# 20V-3V3-Divider.net
KiCad netlist of a schematic drawn in EAGLE
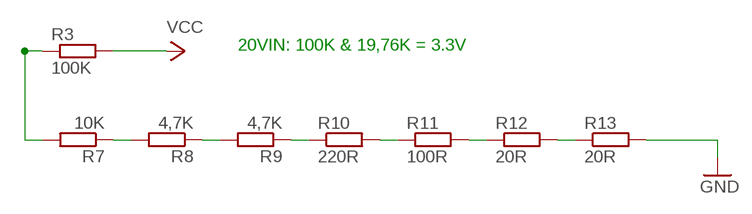
[diagram p0: schematic, sheet 1]

(export (version "E")
  (design (tool "Eeschema 10.0.6"))
  (components
    (comp (ref "R3")
      (value "100K")
      (footprint "eagle-import:0204_7")
      (libsource (lib "eagle-import") (part "R-EU_0204/7"))
    )
    (comp (ref "R7")
      (value "10K")
      (footprint "eagle-import:0204_7")
      (libsource (lib "eagle-import") (part "R-EU_0204/7"))
    )
    (comp (ref "R8")
      (value "4,7K")
      (footprint "eagle-import:0204_7")
      (libsource (lib "eagle-import") (part "R-EU_0204/7"))
    )
    (comp (ref "R9")
      (value "4,7K")
      (footprint "eagle-import:0204_7")
      (libsource (lib "eagle-import") (part "R-EU_0204/7"))
    )
    (comp (ref "R10")
      (value "220R")
      (footprint "eagle-import:0204_7")
      (libsource (lib "eagle-import") (part "R-EU_0204/7"))
    )
    (comp (ref "R11")
      (value "100R")
      (footprint "eagle-import:0204_7")
      (libsource (lib "eagle-import") (part "R-EU_0204/7"))
    )
    (comp (ref "R12")
      (value "20R")
      (footprint "eagle-import:0204_7")
      (libsource (lib "eagle-import") (part "R-EU_0204/7"))
    )
    (comp (ref "R13")
      (value "20R")
      (footprint "eagle-import:0204_7")
      (libsource (lib "eagle-import") (part "R-EU_0204/7"))
    )
  )
  (nets
    (net (code "1") (name "GND") (class "Default")
      (node (ref "R13") (pin "2") (pinfunction "2_2") (pintype "passive"))
    )
    (net (code "2") (name "Net-(R3-Pad1)") (class "Default")
      (node (ref "R3") (pin "1") (pinfunction "1_1") (pintype "passive"))
      (node (ref "R7") (pin "2") (pinfunction "2_2") (pintype "passive"))
    )
    (net (code "3") (name "Net-(R7-Pad1)") (class "Default")
      (node (ref "R7") (pin "1") (pinfunction "1_1") (pintype "passive"))
      (node (ref "R8") (pin "2") (pinfunction "2_2") (pintype "passive"))
    )
    (net (code "4") (name "Net-(R8-Pad1)") (class "Default")
      (node (ref "R8") (pin "1") (pinfunction "1_1") (pintype "passive"))
      (node (ref "R9") (pin "2") (pinfunction "2_2") (pintype "passive"))
    )
    (net (code "5") (name "Net-(R10-Pad1)") (class "Default")
      (node (ref "R10") (pin "1") (pinfunction "1_1") (pintype "passive"))
      (node (ref "R9") (pin "1") (pinfunction "1_1") (pintype "passive"))
    )
    (net (code "6") (name "Net-(R10-Pad2)") (class "Default")
      (node (ref "R10") (pin "2") (pinfunction "2_2") (pintype "passive"))
      (node (ref "R11") (pin "1") (pinfunction "1_1") (pintype "passive"))
    )
    (net (code "7") (name "Net-(R11-Pad2)") (class "Default")
      (node (ref "R11") (pin "2") (pinfunction "2_2") (pintype "passive"))
      (node (ref "R12") (pin "1") (pinfunction "1_1") (pintype "passive"))
    )
    (net (code "8") (name "Net-(R12-Pad2)") (class "Default")
      (node (ref "R12") (pin "2") (pinfunction "2_2") (pintype "passive"))
      (node (ref "R13") (pin "1") (pinfunction "1_1") (pintype "passive"))
    )
    (net (code "9") (name "VCC") (class "Default")
      (node (ref "R3") (pin "2") (pinfunction "2_2") (pintype "passive"))
    )
  )
)
